# CFA.net
KiCad netlist of a schematic drawn in EAGLE
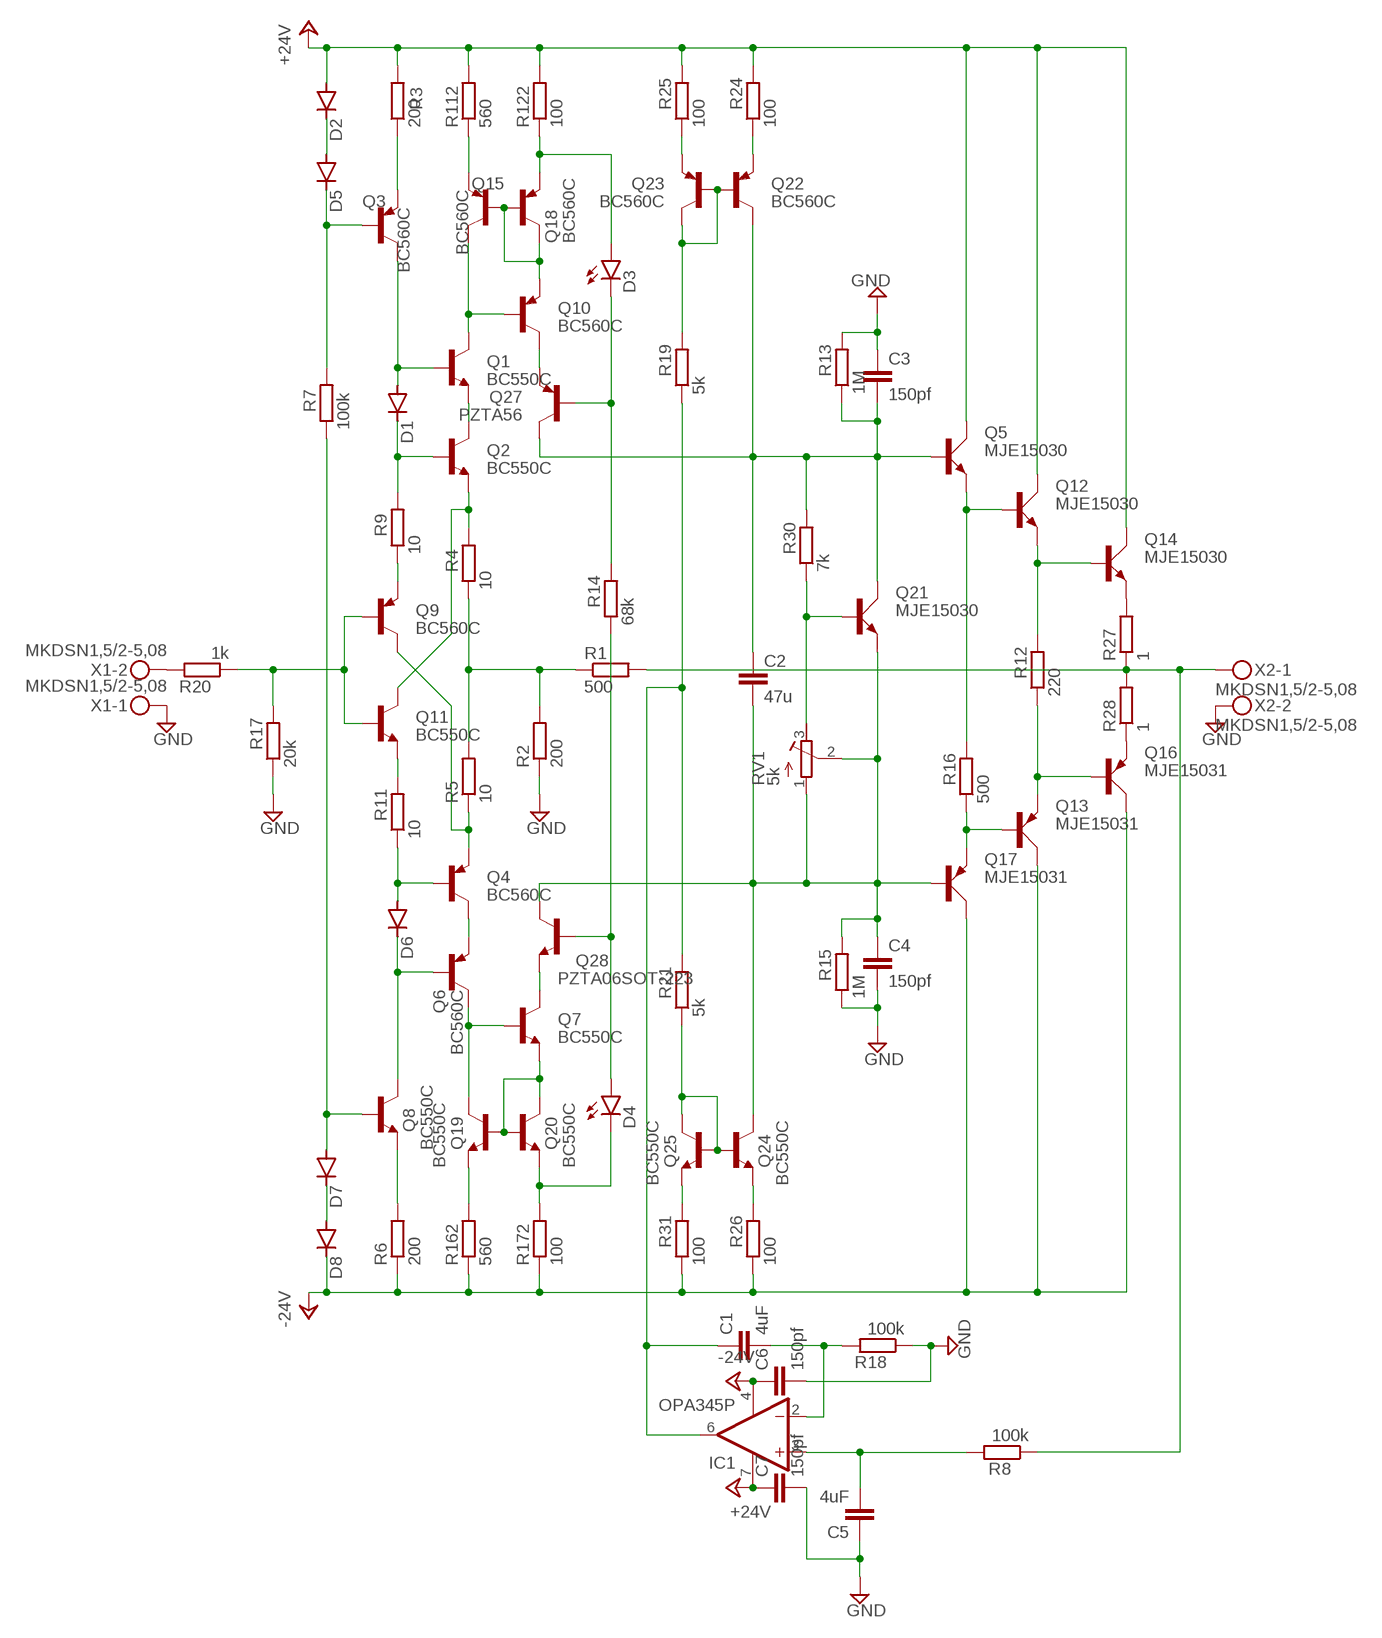
[diagram p0: schematic, sheet 1]

(export (version "E")
  (design (tool "Eeschema 10.0.6"))
  (components
    (comp (ref "C1")
      (value "4uF")
      (footprint "eagle-import:C1210")
      (fields (field (name "SPICEPREFIX") "C"))
      (libsource (lib "eagle-import") (part "C-EUC1210"))
    )
    (comp (ref "C2")
      (value "47u")
      (footprint "eagle-import:C1210")
      (fields (field (name "SPICEPREFIX") "C"))
      (libsource (lib "eagle-import") (part "C-EUC1210"))
    )
    (comp (ref "C3")
      (value "150pf")
      (footprint "eagle-import:C0805")
      (fields (field (name "SPICEPREFIX") "C"))
      (libsource (lib "eagle-import") (part "C-EUC0805"))
    )
    (comp (ref "C4")
      (value "150pf")
      (footprint "eagle-import:C0805")
      (fields (field (name "SPICEPREFIX") "C"))
      (libsource (lib "eagle-import") (part "C-EUC0805"))
    )
    (comp (ref "C5")
      (value "4uF")
      (footprint "eagle-import:C1210")
      (fields (field (name "SPICEPREFIX") "C"))
      (libsource (lib "eagle-import") (part "C-EUC1210"))
    )
    (comp (ref "C6")
      (value "150pf")
      (footprint "eagle-import:C0805")
      (fields (field (name "SPICEPREFIX") "C"))
      (libsource (lib "eagle-import") (part "C-EUC0805"))
    )
    (comp (ref "C7")
      (value "150pf")
      (footprint "eagle-import:C0805")
      (fields (field (name "SPICEPREFIX") "C"))
      (libsource (lib "eagle-import") (part "C-EUC0805"))
    )
    (comp (ref "D1")
      (value "DIODE-SOD80C")
      (footprint "eagle-import:SOD80C")
      (fields (field (name "SPICEPREFIX") "D"))
      (libsource (lib "eagle-import") (part "DIODE-SOD80C"))
    )
    (comp (ref "D2")
      (value "DIODE-SOD80C")
      (footprint "eagle-import:SOD80C")
      (fields (field (name "SPICEPREFIX") "D"))
      (libsource (lib "eagle-import") (part "DIODE-SOD80C"))
    )
    (comp (ref "D3")
      (value "LED5MM")
      (footprint "eagle-import:LED5MM")
      (fields (field (name "SPICEPREFIX") "D"))
      (libsource (lib "eagle-import") (part "LED5MM"))
    )
    (comp (ref "D4")
      (value "LED5MM")
      (footprint "eagle-import:LED5MM")
      (fields (field (name "SPICEPREFIX") "D"))
      (libsource (lib "eagle-import") (part "LED5MM"))
    )
    (comp (ref "D5")
      (value "DIODE-SOD80C")
      (footprint "eagle-import:SOD80C")
      (fields (field (name "SPICEPREFIX") "D"))
      (libsource (lib "eagle-import") (part "DIODE-SOD80C"))
    )
    (comp (ref "D6")
      (value "DIODE-SOD80C")
      (footprint "eagle-import:SOD80C")
      (fields (field (name "SPICEPREFIX") "D"))
      (libsource (lib "eagle-import") (part "DIODE-SOD80C"))
    )
    (comp (ref "D7")
      (value "DIODE-SOD80C")
      (footprint "eagle-import:SOD80C")
      (fields (field (name "SPICEPREFIX") "D"))
      (libsource (lib "eagle-import") (part "DIODE-SOD80C"))
    )
    (comp (ref "D8")
      (value "DIODE-SOD80C")
      (footprint "eagle-import:SOD80C")
      (fields (field (name "SPICEPREFIX") "D"))
      (libsource (lib "eagle-import") (part "DIODE-SOD80C"))
    )
    (comp (ref "IC1")
      (value "OPA345P")
      (footprint "eagle-import:DIL08")
      (fields (field (name "SPICEPREFIX") "X"))
      (libsource (lib "eagle-import") (part "OPAP345"))
    )
    (comp (ref "Q1")
      (value "BC550C")
      (footprint "eagle-import:TO92-EBC")
      (fields (field (name "SPICEPREFIX") "Q"))
      (libsource (lib "eagle-import") (part "BC550C"))
    )
    (comp (ref "Q2")
      (value "BC550C")
      (footprint "eagle-import:TO92-EBC")
      (fields (field (name "SPICEPREFIX") "Q"))
      (libsource (lib "eagle-import") (part "BC550C"))
    )
    (comp (ref "Q3")
      (value "BC560C")
      (footprint "eagle-import:TO92-EBC")
      (fields (field (name "SPICEPREFIX") "Q"))
      (libsource (lib "eagle-import") (part "BC560C"))
    )
    (comp (ref "Q4")
      (value "BC560C")
      (footprint "eagle-import:TO92-EBC")
      (fields (field (name "SPICEPREFIX") "Q"))
      (libsource (lib "eagle-import") (part "BC560C"))
    )
    (comp (ref "Q5")
      (value "MJE15030")
      (footprint "eagle-import:TO220AV")
      (fields (field (name "SPICEPREFIX") "Q"))
      (libsource (lib "eagle-import") (part "MJE3055"))
    )
    (comp (ref "Q6")
      (value "BC560C")
      (footprint "eagle-import:TO92-EBC")
      (fields (field (name "SPICEPREFIX") "Q"))
      (libsource (lib "eagle-import") (part "BC560C"))
    )
    (comp (ref "Q7")
      (value "BC550C")
      (footprint "eagle-import:TO92-EBC")
      (fields (field (name "SPICEPREFIX") "Q"))
      (libsource (lib "eagle-import") (part "BC550C"))
    )
    (comp (ref "Q8")
      (value "BC550C")
      (footprint "eagle-import:TO92-EBC")
      (fields (field (name "SPICEPREFIX") "Q"))
      (libsource (lib "eagle-import") (part "BC550C"))
    )
    (comp (ref "Q9")
      (value "BC560C")
      (footprint "eagle-import:TO92-EBC")
      (fields (field (name "SPICEPREFIX") "Q"))
      (libsource (lib "eagle-import") (part "BC560C"))
    )
    (comp (ref "Q10")
      (value "BC560C")
      (footprint "eagle-import:TO92-EBC")
      (fields (field (name "SPICEPREFIX") "Q"))
      (libsource (lib "eagle-import") (part "BC560C"))
    )
    (comp (ref "Q11")
      (value "BC550C")
      (footprint "eagle-import:TO92-EBC")
      (fields (field (name "SPICEPREFIX") "Q"))
      (libsource (lib "eagle-import") (part "BC550C"))
    )
    (comp (ref "Q12")
      (value "MJE15030")
      (footprint "eagle-import:TO220AV")
      (fields (field (name "SPICEPREFIX") "Q"))
      (libsource (lib "eagle-import") (part "MJE3055"))
    )
    (comp (ref "Q13")
      (value "MJE15031")
      (footprint "eagle-import:TO220AV")
      (fields (field (name "SPICEPREFIX") "Q"))
      (libsource (lib "eagle-import") (part "MJE2955"))
    )
    (comp (ref "Q14")
      (value "MJE15030")
      (footprint "eagle-import:TO220AV")
      (fields (field (name "SPICEPREFIX") "Q"))
      (libsource (lib "eagle-import") (part "MJE3055"))
    )
    (comp (ref "Q15")
      (value "BC560C")
      (footprint "eagle-import:TO92-EBC")
      (fields (field (name "SPICEPREFIX") "Q"))
      (libsource (lib "eagle-import") (part "BC560C"))
    )
    (comp (ref "Q16")
      (value "MJE15031")
      (footprint "eagle-import:TO220AV")
      (fields (field (name "SPICEPREFIX") "Q"))
      (libsource (lib "eagle-import") (part "MJE2955"))
    )
    (comp (ref "Q17")
      (value "MJE15031")
      (footprint "eagle-import:TO220AV")
      (fields (field (name "SPICEPREFIX") "Q"))
      (libsource (lib "eagle-import") (part "MJE2955"))
    )
    (comp (ref "Q18")
      (value "BC560C")
      (footprint "eagle-import:TO92-EBC")
      (fields (field (name "SPICEPREFIX") "Q"))
      (libsource (lib "eagle-import") (part "BC560C"))
    )
    (comp (ref "Q19")
      (value "BC550C")
      (footprint "eagle-import:TO92-EBC")
      (fields (field (name "SPICEPREFIX") "Q"))
      (libsource (lib "eagle-import") (part "BC550C"))
    )
    (comp (ref "Q20")
      (value "BC550C")
      (footprint "eagle-import:TO92-EBC")
      (fields (field (name "SPICEPREFIX") "Q"))
      (libsource (lib "eagle-import") (part "BC550C"))
    )
    (comp (ref "Q21")
      (value "MJE15030")
      (footprint "eagle-import:TO220AV")
      (fields (field (name "SPICEPREFIX") "Q"))
      (libsource (lib "eagle-import") (part "MJE3055"))
    )
    (comp (ref "Q22")
      (value "BC560C")
      (footprint "eagle-import:TO92-EBC")
      (fields (field (name "SPICEPREFIX") "Q"))
      (libsource (lib "eagle-import") (part "BC560C"))
    )
    (comp (ref "Q23")
      (value "BC560C")
      (footprint "eagle-import:TO92-EBC")
      (fields (field (name "SPICEPREFIX") "Q"))
      (libsource (lib "eagle-import") (part "BC560C"))
    )
    (comp (ref "Q24")
      (value "BC550C")
      (footprint "eagle-import:TO92-EBC")
      (fields (field (name "SPICEPREFIX") "Q"))
      (libsource (lib "eagle-import") (part "BC550C"))
    )
    (comp (ref "Q25")
      (value "BC550C")
      (footprint "eagle-import:TO92-EBC")
      (fields (field (name "SPICEPREFIX") "Q"))
      (libsource (lib "eagle-import") (part "BC550C"))
    )
    (comp (ref "Q27")
      (value "PZTA56")
      (footprint "eagle-import:SOT223")
      (fields (field (name "SPICEPREFIX") "Q"))
      (libsource (lib "eagle-import") (part "PZTA56"))
    )
    (comp (ref "Q28")
      (value "PZTA06SOT-223")
      (footprint "eagle-import:SOT223")
      (fields (field (name "SPICEPREFIX") "Q"))
      (libsource (lib "eagle-import") (part "PZTA06SOT-223"))
    )
    (comp (ref "R1")
      (value "500")
      (footprint "eagle-import:MINI_MELF-0204R")
      (fields (field (name "SPICEPREFIX") "R"))
      (libsource (lib "eagle-import") (part "R-EU_MELF0204R"))
    )
    (comp (ref "R2")
      (value "200")
      (footprint "eagle-import:MINI_MELF-0204R")
      (fields (field (name "SPICEPREFIX") "R"))
      (libsource (lib "eagle-import") (part "R-EU_MELF0204R"))
    )
    (comp (ref "R3")
      (value "200")
      (footprint "eagle-import:MINI_MELF-0204R")
      (fields (field (name "SPICEPREFIX") "R"))
      (libsource (lib "eagle-import") (part "R-EU_MELF0204R"))
    )
    (comp (ref "R4")
      (value "10")
      (footprint "eagle-import:MINI_MELF-0204R")
      (fields (field (name "SPICEPREFIX") "R"))
      (libsource (lib "eagle-import") (part "R-EU_MELF0204R"))
    )
    (comp (ref "R5")
      (value "10")
      (footprint "eagle-import:MINI_MELF-0204R")
      (fields (field (name "SPICEPREFIX") "R"))
      (libsource (lib "eagle-import") (part "R-EU_MELF0204R"))
    )
    (comp (ref "R6")
      (value "200")
      (footprint "eagle-import:MINI_MELF-0204R")
      (fields (field (name "SPICEPREFIX") "R"))
      (libsource (lib "eagle-import") (part "R-EU_MELF0204R"))
    )
    (comp (ref "R7")
      (value "100k")
      (footprint "eagle-import:MINI_MELF-0204R")
      (fields (field (name "SPICEPREFIX") "R"))
      (libsource (lib "eagle-import") (part "R-EU_MELF0204R"))
    )
    (comp (ref "R8")
      (value "100k")
      (footprint "eagle-import:MINI_MELF-0204R")
      (fields (field (name "SPICEPREFIX") "R"))
      (libsource (lib "eagle-import") (part "R-EU_MELF0204R"))
    )
    (comp (ref "R9")
      (value "10")
      (footprint "eagle-import:MINI_MELF-0204R")
      (fields (field (name "SPICEPREFIX") "R"))
      (libsource (lib "eagle-import") (part "R-EU_MELF0204R"))
    )
    (comp (ref "R11")
      (value "10")
      (footprint "eagle-import:MINI_MELF-0204R")
      (fields (field (name "SPICEPREFIX") "R"))
      (libsource (lib "eagle-import") (part "R-EU_MELF0204R"))
    )
    (comp (ref "R12")
      (value "220")
      (footprint "eagle-import:MINI_MELF-0204R")
      (fields (field (name "SPICEPREFIX") "R"))
      (libsource (lib "eagle-import") (part "R-EU_MELF0204R"))
    )
    (comp (ref "R13")
      (value "1M")
      (footprint "eagle-import:MINI_MELF-0204R")
      (fields (field (name "SPICEPREFIX") "R"))
      (libsource (lib "eagle-import") (part "R-EU_MELF0204R"))
    )
    (comp (ref "R14")
      (value "68k")
      (footprint "eagle-import:MINI_MELF-0204R")
      (fields (field (name "SPICEPREFIX") "R"))
      (libsource (lib "eagle-import") (part "R-EU_MELF0204R"))
    )
    (comp (ref "R15")
      (value "1M")
      (footprint "eagle-import:MINI_MELF-0204R")
      (fields (field (name "SPICEPREFIX") "R"))
      (libsource (lib "eagle-import") (part "R-EU_MELF0204R"))
    )
    (comp (ref "R16")
      (value "500")
      (footprint "eagle-import:MINI_MELF-0204R")
      (fields (field (name "SPICEPREFIX") "R"))
      (libsource (lib "eagle-import") (part "R-EU_MELF0204R"))
    )
    (comp (ref "R17")
      (value "20k")
      (footprint "eagle-import:MINI_MELF-0204R")
      (fields (field (name "SPICEPREFIX") "R"))
      (libsource (lib "eagle-import") (part "R-EU_MELF0204R"))
    )
    (comp (ref "R18")
      (value "100k")
      (footprint "eagle-import:MINI_MELF-0204R")
      (fields (field (name "SPICEPREFIX") "R"))
      (libsource (lib "eagle-import") (part "R-EU_MELF0204R"))
    )
    (comp (ref "R19")
      (value "5k")
      (footprint "eagle-import:MINI_MELF-0204R")
      (fields (field (name "SPICEPREFIX") "R"))
      (libsource (lib "eagle-import") (part "R-EU_MELF0204R"))
    )
    (comp (ref "R20")
      (value "1k")
      (footprint "eagle-import:MINI_MELF-0204R")
      (fields (field (name "SPICEPREFIX") "R"))
      (libsource (lib "eagle-import") (part "R-EU_MELF0204R"))
    )
    (comp (ref "R21")
      (value "5k")
      (footprint "eagle-import:MINI_MELF-0204R")
      (fields (field (name "SPICEPREFIX") "R"))
      (libsource (lib "eagle-import") (part "R-EU_MELF0204R"))
    )
    (comp (ref "R24")
      (value "100")
      (footprint "eagle-import:MINI_MELF-0204R")
      (fields (field (name "SPICEPREFIX") "R"))
      (libsource (lib "eagle-import") (part "R-EU_MELF0204R"))
    )
    (comp (ref "R25")
      (value "100")
      (footprint "eagle-import:MINI_MELF-0204R")
      (fields (field (name "SPICEPREFIX") "R"))
      (libsource (lib "eagle-import") (part "R-EU_MELF0204R"))
    )
    (comp (ref "R26")
      (value "100")
      (footprint "eagle-import:MINI_MELF-0204R")
      (fields (field (name "SPICEPREFIX") "R"))
      (libsource (lib "eagle-import") (part "R-EU_MELF0204R"))
    )
    (comp (ref "R27")
      (value "1")
      (footprint "eagle-import:0617_22")
      (fields (field (name "SPICEPREFIX") "R"))
      (libsource (lib "eagle-import") (part "R-EU_0617/22"))
    )
    (comp (ref "R28")
      (value "1")
      (footprint "eagle-import:0617_22")
      (fields (field (name "SPICEPREFIX") "R"))
      (libsource (lib "eagle-import") (part "R-EU_0617/22"))
    )
    (comp (ref "R30")
      (value "7k")
      (footprint "eagle-import:MINI_MELF-0204R")
      (fields (field (name "SPICEPREFIX") "R"))
      (libsource (lib "eagle-import") (part "R-EU_MELF0204R"))
    )
    (comp (ref "R31")
      (value "100")
      (footprint "eagle-import:MINI_MELF-0204R")
      (fields (field (name "SPICEPREFIX") "R"))
      (libsource (lib "eagle-import") (part "R-EU_MELF0204R"))
    )
    (comp (ref "R112")
      (value "560")
      (footprint "eagle-import:MINI_MELF-0204R")
      (fields (field (name "SPICEPREFIX") "R"))
      (libsource (lib "eagle-import") (part "R-EU_MELF0204R"))
    )
    (comp (ref "R122")
      (value "100")
      (footprint "eagle-import:MINI_MELF-0204R")
      (fields (field (name "SPICEPREFIX") "R"))
      (libsource (lib "eagle-import") (part "R-EU_MELF0204R"))
    )
    (comp (ref "R162")
      (value "560")
      (footprint "eagle-import:MINI_MELF-0204R")
      (fields (field (name "SPICEPREFIX") "R"))
      (libsource (lib "eagle-import") (part "R-EU_MELF0204R"))
    )
    (comp (ref "R172")
      (value "100")
      (footprint "eagle-import:MINI_MELF-0204R")
      (fields (field (name "SPICEPREFIX") "R"))
      (libsource (lib "eagle-import") (part "R-EU_MELF0204R"))
    )
    (comp (ref "RV1")
      (value "5k")
      (footprint "eagle-import:RTRIM3296W")
      (fields (field (name "SPICEPREFIX") "Z"))
      (libsource (lib "eagle-import") (part "R-TRIMM3296W"))
    )
    (comp (ref "X1")
      (value "MKDSN1,5/2-5,08")
      (footprint "eagle-import:MKDSN1,5_2-5,08")
      (libsource (lib "eagle-import") (part "MKDSN1,5/2-5,08"))
    )
    (comp (ref "X2")
      (value "MKDSN1,5/2-5,08")
      (footprint "eagle-import:MKDSN1,5_2-5,08")
      (libsource (lib "eagle-import") (part "MKDSN1,5/2-5,08"))
    )
  )
  (nets
    (net (code "1") (name "+24V") (class "Default")
      (node (ref "C7") (pin "1") (pinfunction "1_1") (pintype "passive"))
      (node (ref "D2") (pin "A") (pinfunction "A_A") (pintype "passive"))
      (node (ref "IC1") (pin "7") (pinfunction "V+_7") (pintype "power_in"))
      (node (ref "Q12") (pin "C") (pinfunction "C_C") (pintype "passive"))
      (node (ref "Q14") (pin "C") (pinfunction "C_C") (pintype "passive"))
      (node (ref "Q5") (pin "C") (pinfunction "C_C") (pintype "passive"))
      (node (ref "R112") (pin "2") (pinfunction "2_2") (pintype "passive"))
      (node (ref "R122") (pin "2") (pinfunction "2_2") (pintype "passive"))
      (node (ref "R24") (pin "2") (pinfunction "2_2") (pintype "passive"))
      (node (ref "R25") (pin "2") (pinfunction "2_2") (pintype "passive"))
      (node (ref "R3") (pin "2") (pinfunction "2_2") (pintype "passive"))
    )
    (net (code "2") (name "-24V") (class "Default")
      (node (ref "C6") (pin "1") (pinfunction "1_1") (pintype "passive"))
      (node (ref "D8") (pin "C") (pinfunction "C_C") (pintype "passive"))
      (node (ref "IC1") (pin "4") (pinfunction "V-_4") (pintype "power_in"))
      (node (ref "Q13") (pin "C") (pinfunction "C_C") (pintype "passive"))
      (node (ref "Q16") (pin "C") (pinfunction "C_C") (pintype "passive"))
      (node (ref "Q17") (pin "C") (pinfunction "C_C") (pintype "passive"))
      (node (ref "R162") (pin "1") (pinfunction "1_1") (pintype "passive"))
      (node (ref "R172") (pin "1") (pinfunction "1_1") (pintype "passive"))
      (node (ref "R26") (pin "1") (pinfunction "1_1") (pintype "passive"))
      (node (ref "R31") (pin "1") (pinfunction "1_1") (pintype "passive"))
      (node (ref "R6") (pin "1") (pinfunction "1_1") (pintype "passive"))
    )
    (net (code "3") (name "GND") (class "Default")
      (node (ref "C3") (pin "1") (pinfunction "1_1") (pintype "passive"))
      (node (ref "C4") (pin "2") (pinfunction "2_2") (pintype "passive"))
      (node (ref "C5") (pin "1") (pinfunction "1_1") (pintype "passive"))
      (node (ref "C6") (pin "2") (pinfunction "2_2") (pintype "passive"))
      (node (ref "C7") (pin "2") (pinfunction "2_2") (pintype "passive"))
      (node (ref "R13") (pin "2") (pinfunction "2_2") (pintype "passive"))
      (node (ref "R15") (pin "1") (pinfunction "1_1") (pintype "passive"))
      (node (ref "R17") (pin "1") (pinfunction "1_1") (pintype "passive"))
      (node (ref "R18") (pin "1") (pinfunction "1_1") (pintype "passive"))
      (node (ref "R2") (pin "1") (pinfunction "1_1") (pintype "passive"))
      (node (ref "X1") (pin "1") (pinfunction "KL_1") (pintype "passive"))
      (node (ref "X2") (pin "2") (pinfunction "KL_2") (pintype "passive"))
    )
    (net (code "4") (name "Net-(C2-Pad1)") (class "Default")
      (node (ref "C2") (pin "1") (pinfunction "1_1") (pintype "passive"))
      (node (ref "C3") (pin "2") (pinfunction "2_2") (pintype "passive"))
      (node (ref "Q21") (pin "C") (pinfunction "C_C") (pintype "passive"))
      (node (ref "Q22") (pin "C") (pinfunction "C_C") (pintype "passive"))
      (node (ref "Q27") (pin "2") (pinfunction "C_2") (pintype "passive"))
      (node (ref "Q27") (pin "4") (pinfunction "C_4") (pintype "passive"))
      (node (ref "Q5") (pin "B") (pinfunction "B_B") (pintype "passive"))
      (node (ref "R13") (pin "1") (pinfunction "1_1") (pintype "passive"))
      (node (ref "R30") (pin "2") (pinfunction "2_2") (pintype "passive"))
    )
    (net (code "5") (name "Net-(D1-PadA)") (class "Default")
      (node (ref "D1") (pin "A") (pinfunction "A_A") (pintype "passive"))
      (node (ref "Q1") (pin "B") (pinfunction "B_B") (pintype "passive"))
      (node (ref "Q3") (pin "C") (pinfunction "C_C") (pintype "passive"))
    )
    (net (code "6") (name "Net-(D1-PadC)") (class "Default")
      (node (ref "D1") (pin "C") (pinfunction "C_C") (pintype "passive"))
      (node (ref "Q2") (pin "B") (pinfunction "B_B") (pintype "passive"))
      (node (ref "R9") (pin "2") (pinfunction "2_2") (pintype "passive"))
    )
    (net (code "7") (name "Net-(D2-PadC)") (class "Default")
      (node (ref "D2") (pin "C") (pinfunction "C_C") (pintype "passive"))
      (node (ref "D5") (pin "A") (pinfunction "A_A") (pintype "passive"))
    )
    (net (code "8") (name "Net-(D3-C)") (class "Default")
      (node (ref "D3") (pin "K") (pinfunction "C_K") (pintype "passive"))
      (node (ref "Q27") (pin "1") (pinfunction "B_1") (pintype "passive"))
      (node (ref "R14") (pin "2") (pinfunction "2_2") (pintype "passive"))
    )
    (net (code "9") (name "Net-(D3-PadA)") (class "Default")
      (node (ref "D3") (pin "A") (pinfunction "A_A") (pintype "passive"))
      (node (ref "Q18") (pin "E") (pinfunction "E_E") (pintype "passive"))
      (node (ref "R122") (pin "1") (pinfunction "1_1") (pintype "passive"))
    )
    (net (code "10") (name "Net-(D4-C)") (class "Default")
      (node (ref "D4") (pin "K") (pinfunction "C_K") (pintype "passive"))
      (node (ref "Q20") (pin "E") (pinfunction "E_E") (pintype "passive"))
      (node (ref "R172") (pin "2") (pinfunction "2_2") (pintype "passive"))
    )
    (net (code "11") (name "Net-(D5-PadC)") (class "Default")
      (node (ref "D5") (pin "C") (pinfunction "C_C") (pintype "passive"))
      (node (ref "Q3") (pin "B") (pinfunction "B_B") (pintype "passive"))
      (node (ref "R7") (pin "2") (pinfunction "2_2") (pintype "passive"))
    )
    (net (code "12") (name "Net-(D6-PadA)") (class "Default")
      (node (ref "D6") (pin "A") (pinfunction "A_A") (pintype "passive"))
      (node (ref "Q4") (pin "B") (pinfunction "B_B") (pintype "passive"))
      (node (ref "R11") (pin "1") (pinfunction "1_1") (pintype "passive"))
    )
    (net (code "13") (name "Net-(D6-PadC)") (class "Default")
      (node (ref "D6") (pin "C") (pinfunction "C_C") (pintype "passive"))
      (node (ref "Q6") (pin "B") (pinfunction "B_B") (pintype "passive"))
      (node (ref "Q8") (pin "C") (pinfunction "C_C") (pintype "passive"))
    )
    (net (code "14") (name "Net-(D7-PadA)") (class "Default")
      (node (ref "D7") (pin "A") (pinfunction "A_A") (pintype "passive"))
      (node (ref "Q8") (pin "B") (pinfunction "B_B") (pintype "passive"))
      (node (ref "R7") (pin "1") (pinfunction "1_1") (pintype "passive"))
    )
    (net (code "15") (name "Net-(D7-PadC)") (class "Default")
      (node (ref "D7") (pin "C") (pinfunction "C_C") (pintype "passive"))
      (node (ref "D8") (pin "A") (pinfunction "A_A") (pintype "passive"))
    )
    (net (code "16") (name "Net-(IC1-+IN)") (class "Default")
      (node (ref "C5") (pin "2") (pinfunction "2_2") (pintype "passive"))
      (node (ref "IC1") (pin "3") (pinfunction "+IN_3") (pintype "input"))
      (node (ref "R8") (pin "2") (pinfunction "2_2") (pintype "passive"))
    )
    (net (code "17") (name "Net-(IC1--IN)") (class "Default")
      (node (ref "C1") (pin "2") (pinfunction "2_2") (pintype "passive"))
      (node (ref "IC1") (pin "2") (pinfunction "-IN_2") (pintype "input"))
      (node (ref "R18") (pin "2") (pinfunction "2_2") (pintype "passive"))
    )
    (net (code "18") (name "Net-(IC1-OUT)") (class "Default")
      (node (ref "C1") (pin "1") (pinfunction "1_1") (pintype "passive"))
      (node (ref "IC1") (pin "6") (pinfunction "OUT_6") (pintype "output"))
      (node (ref "R19") (pin "1") (pinfunction "1_1") (pintype "passive"))
      (node (ref "R21") (pin "2") (pinfunction "2_2") (pintype "passive"))
    )
    (net (code "19") (name "Net-(Q1-PadC)") (class "Default")
      (node (ref "Q1") (pin "C") (pinfunction "C_C") (pintype "passive"))
      (node (ref "Q10") (pin "B") (pinfunction "B_B") (pintype "passive"))
      (node (ref "Q15") (pin "C") (pinfunction "C_C") (pintype "passive"))
    )
    (net (code "20") (name "Net-(Q1-PadE)") (class "Default")
      (node (ref "Q1") (pin "E") (pinfunction "E_E") (pintype "passive"))
      (node (ref "Q2") (pin "C") (pinfunction "C_C") (pintype "passive"))
    )
    (net (code "21") (name "Net-(Q3-PadE)") (class "Default")
      (node (ref "Q3") (pin "E") (pinfunction "E_E") (pintype "passive"))
      (node (ref "R3") (pin "1") (pinfunction "1_1") (pintype "passive"))
    )
    (net (code "22") (name "Net-(Q4-PadC)") (class "Default")
      (node (ref "Q4") (pin "C") (pinfunction "C_C") (pintype "passive"))
      (node (ref "Q6") (pin "E") (pinfunction "E_E") (pintype "passive"))
    )
    (net (code "23") (name "Net-(Q4-PadE)") (class "Default")
      (node (ref "Q4") (pin "E") (pinfunction "E_E") (pintype "passive"))
      (node (ref "Q9") (pin "C") (pinfunction "C_C") (pintype "passive"))
      (node (ref "R5") (pin "1") (pinfunction "1_1") (pintype "passive"))
    )
    (net (code "24") (name "Net-(Q8-PadE)") (class "Default")
      (node (ref "Q8") (pin "E") (pinfunction "E_E") (pintype "passive"))
      (node (ref "R6") (pin "2") (pinfunction "2_2") (pintype "passive"))
    )
    (net (code "25") (name "Net-(Q9-PadE)") (class "Default")
      (node (ref "Q9") (pin "E") (pinfunction "E_E") (pintype "passive"))
      (node (ref "R9") (pin "1") (pinfunction "1_1") (pintype "passive"))
    )
    (net (code "26") (name "Net-(Q10-PadE)") (class "Default")
      (node (ref "Q10") (pin "E") (pinfunction "E_E") (pintype "passive"))
      (node (ref "Q15") (pin "B") (pinfunction "B_B") (pintype "passive"))
      (node (ref "Q18") (pin "B") (pinfunction "B_B") (pintype "passive"))
      (node (ref "Q18") (pin "C") (pinfunction "C_C") (pintype "passive"))
    )
    (net (code "27") (name "Net-(Q11-PadB)") (class "Default")
      (node (ref "Q11") (pin "B") (pinfunction "B_B") (pintype "passive"))
      (node (ref "Q9") (pin "B") (pinfunction "B_B") (pintype "passive"))
      (node (ref "R17") (pin "2") (pinfunction "2_2") (pintype "passive"))
      (node (ref "R20") (pin "1") (pinfunction "1_1") (pintype "passive"))
    )
    (net (code "28") (name "Net-(Q11-PadC)") (class "Default")
      (node (ref "Q11") (pin "C") (pinfunction "C_C") (pintype "passive"))
      (node (ref "Q2") (pin "E") (pinfunction "E_E") (pintype "passive"))
      (node (ref "R4") (pin "2") (pinfunction "2_2") (pintype "passive"))
    )
    (net (code "29") (name "Net-(Q11-PadE)") (class "Default")
      (node (ref "Q11") (pin "E") (pinfunction "E_E") (pintype "passive"))
      (node (ref "R11") (pin "2") (pinfunction "2_2") (pintype "passive"))
    )
    (net (code "30") (name "Net-(Q12-PadB)") (class "Default")
      (node (ref "Q12") (pin "B") (pinfunction "B_B") (pintype "passive"))
      (node (ref "Q5") (pin "E") (pinfunction "E_E") (pintype "passive"))
      (node (ref "R16") (pin "2") (pinfunction "2_2") (pintype "passive"))
    )
    (net (code "31") (name "Net-(Q12-PadE)") (class "Default")
      (node (ref "Q12") (pin "E") (pinfunction "E_E") (pintype "passive"))
      (node (ref "Q14") (pin "B") (pinfunction "B_B") (pintype "passive"))
      (node (ref "R12") (pin "2") (pinfunction "2_2") (pintype "passive"))
    )
    (net (code "32") (name "Net-(Q13-PadB)") (class "Default")
      (node (ref "Q13") (pin "B") (pinfunction "B_B") (pintype "passive"))
      (node (ref "Q17") (pin "E") (pinfunction "E_E") (pintype "passive"))
      (node (ref "R16") (pin "1") (pinfunction "1_1") (pintype "passive"))
    )
    (net (code "33") (name "Net-(Q13-PadE)") (class "Default")
      (node (ref "Q13") (pin "E") (pinfunction "E_E") (pintype "passive"))
      (node (ref "Q16") (pin "B") (pinfunction "B_B") (pintype "passive"))
      (node (ref "R12") (pin "1") (pinfunction "1_1") (pintype "passive"))
    )
    (net (code "34") (name "Net-(Q14-PadE)") (class "Default")
      (node (ref "Q14") (pin "E") (pinfunction "E_E") (pintype "passive"))
      (node (ref "R27") (pin "2") (pinfunction "2_2") (pintype "passive"))
    )
    (net (code "35") (name "Net-(Q15-PadE)") (class "Default")
      (node (ref "Q15") (pin "E") (pinfunction "E_E") (pintype "passive"))
      (node (ref "R112") (pin "1") (pinfunction "1_1") (pintype "passive"))
    )
    (net (code "36") (name "Net-(Q16-PadE)") (class "Default")
      (node (ref "Q16") (pin "E") (pinfunction "E_E") (pintype "passive"))
      (node (ref "R28") (pin "1") (pinfunction "1_1") (pintype "passive"))
    )
    (net (code "37") (name "Net-(Q19-PadB)") (class "Default")
      (node (ref "Q19") (pin "B") (pinfunction "B_B") (pintype "passive"))
      (node (ref "Q20") (pin "B") (pinfunction "B_B") (pintype "passive"))
      (node (ref "Q20") (pin "C") (pinfunction "C_C") (pintype "passive"))
      (node (ref "Q7") (pin "E") (pinfunction "E_E") (pintype "passive"))
    )
    (net (code "38") (name "Net-(Q19-PadC)") (class "Default")
      (node (ref "Q19") (pin "C") (pinfunction "C_C") (pintype "passive"))
      (node (ref "Q6") (pin "C") (pinfunction "C_C") (pintype "passive"))
      (node (ref "Q7") (pin "B") (pinfunction "B_B") (pintype "passive"))
    )
    (net (code "39") (name "Net-(Q19-PadE)") (class "Default")
      (node (ref "Q19") (pin "E") (pinfunction "E_E") (pintype "passive"))
      (node (ref "R162") (pin "2") (pinfunction "2_2") (pintype "passive"))
    )
    (net (code "40") (name "Net-(Q22-PadB)") (class "Default")
      (node (ref "Q22") (pin "B") (pinfunction "B_B") (pintype "passive"))
      (node (ref "Q23") (pin "B") (pinfunction "B_B") (pintype "passive"))
      (node (ref "Q23") (pin "C") (pinfunction "C_C") (pintype "passive"))
      (node (ref "R19") (pin "2") (pinfunction "2_2") (pintype "passive"))
    )
    (net (code "41") (name "Net-(Q22-PadE)") (class "Default")
      (node (ref "Q22") (pin "E") (pinfunction "E_E") (pintype "passive"))
      (node (ref "R24") (pin "1") (pinfunction "1_1") (pintype "passive"))
    )
    (net (code "42") (name "Net-(Q23-PadE)") (class "Default")
      (node (ref "Q23") (pin "E") (pinfunction "E_E") (pintype "passive"))
      (node (ref "R25") (pin "1") (pinfunction "1_1") (pintype "passive"))
    )
    (net (code "43") (name "Net-(Q24-PadB)") (class "Default")
      (node (ref "Q24") (pin "B") (pinfunction "B_B") (pintype "passive"))
      (node (ref "Q25") (pin "B") (pinfunction "B_B") (pintype "passive"))
      (node (ref "Q25") (pin "C") (pinfunction "C_C") (pintype "passive"))
      (node (ref "R21") (pin "1") (pinfunction "1_1") (pintype "passive"))
    )
    (net (code "44") (name "Net-(Q24-PadE)") (class "Default")
      (node (ref "Q24") (pin "E") (pinfunction "E_E") (pintype "passive"))
      (node (ref "R26") (pin "2") (pinfunction "2_2") (pintype "passive"))
    )
    (net (code "45") (name "Net-(Q25-PadE)") (class "Default")
      (node (ref "Q25") (pin "E") (pinfunction "E_E") (pintype "passive"))
      (node (ref "R31") (pin "2") (pinfunction "2_2") (pintype "passive"))
    )
    (net (code "46") (name "Net-(Q27-E)") (class "Default")
      (node (ref "Q10") (pin "C") (pinfunction "C_C") (pintype "passive"))
      (node (ref "Q27") (pin "3") (pinfunction "E_3") (pintype "passive"))
    )
    (net (code "47") (name "Net-(Q28-B)") (class "Default")
      (node (ref "D4") (pin "A") (pinfunction "A_A") (pintype "passive"))
      (node (ref "Q28") (pin "1") (pinfunction "B_1") (pintype "passive"))
      (node (ref "R14") (pin "1") (pinfunction "1_1") (pintype "passive"))
    )
    (net (code "48") (name "Net-(Q28-E)") (class "Default")
      (node (ref "Q28") (pin "3") (pinfunction "E_3") (pintype "passive"))
      (node (ref "Q7") (pin "C") (pinfunction "C_C") (pintype "passive"))
    )
    (net (code "49") (name "Net-(R1-Pad1)") (class "Default")
      (node (ref "R1") (pin "1") (pinfunction "1_1") (pintype "passive"))
      (node (ref "R2") (pin "2") (pinfunction "2_2") (pintype "passive"))
      (node (ref "R4") (pin "1") (pinfunction "1_1") (pintype "passive"))
      (node (ref "R5") (pin "2") (pinfunction "2_2") (pintype "passive"))
    )
    (net (code "50") (name "Net-(RV1-A)") (class "Default")
      (node (ref "C2") (pin "2") (pinfunction "2_2") (pintype "passive"))
      (node (ref "C4") (pin "1") (pinfunction "1_1") (pintype "passive"))
      (node (ref "Q17") (pin "B") (pinfunction "B_B") (pintype "passive"))
      (node (ref "Q21") (pin "E") (pinfunction "E_E") (pintype "passive"))
      (node (ref "Q24") (pin "C") (pinfunction "C_C") (pintype "passive"))
      (node (ref "Q28") (pin "2") (pinfunction "C_2") (pintype "passive"))
      (node (ref "Q28") (pin "4") (pinfunction "C_4") (pintype "passive"))
      (node (ref "R15") (pin "2") (pinfunction "2_2") (pintype "passive"))
      (node (ref "RV1") (pin "1") (pinfunction "A_1") (pintype "passive"))
      (node (ref "RV1") (pin "2") (pinfunction "S_2") (pintype "passive"))
    )
    (net (code "51") (name "Net-(RV1-E)") (class "Default")
      (node (ref "Q21") (pin "B") (pinfunction "B_B") (pintype "passive"))
      (node (ref "R30") (pin "1") (pinfunction "1_1") (pintype "passive"))
      (node (ref "RV1") (pin "3") (pinfunction "E_3") (pintype "passive"))
    )
    (net (code "52") (name "Net-(X1B-KL)") (class "Default")
      (node (ref "R20") (pin "2") (pinfunction "2_2") (pintype "passive"))
      (node (ref "X1") (pin "2") (pinfunction "KL_2") (pintype "passive"))
    )
    (net (code "53") (name "Net-(X2A-KL)") (class "Default")
      (node (ref "R1") (pin "2") (pinfunction "2_2") (pintype "passive"))
      (node (ref "R27") (pin "1") (pinfunction "1_1") (pintype "passive"))
      (node (ref "R28") (pin "2") (pinfunction "2_2") (pintype "passive"))
      (node (ref "R8") (pin "1") (pinfunction "1_1") (pintype "passive"))
      (node (ref "X2") (pin "1") (pinfunction "KL_1") (pintype "passive"))
    )
  )
)
